# MainBoard.net
KiCad netlist of a schematic drawn in Altium Designer
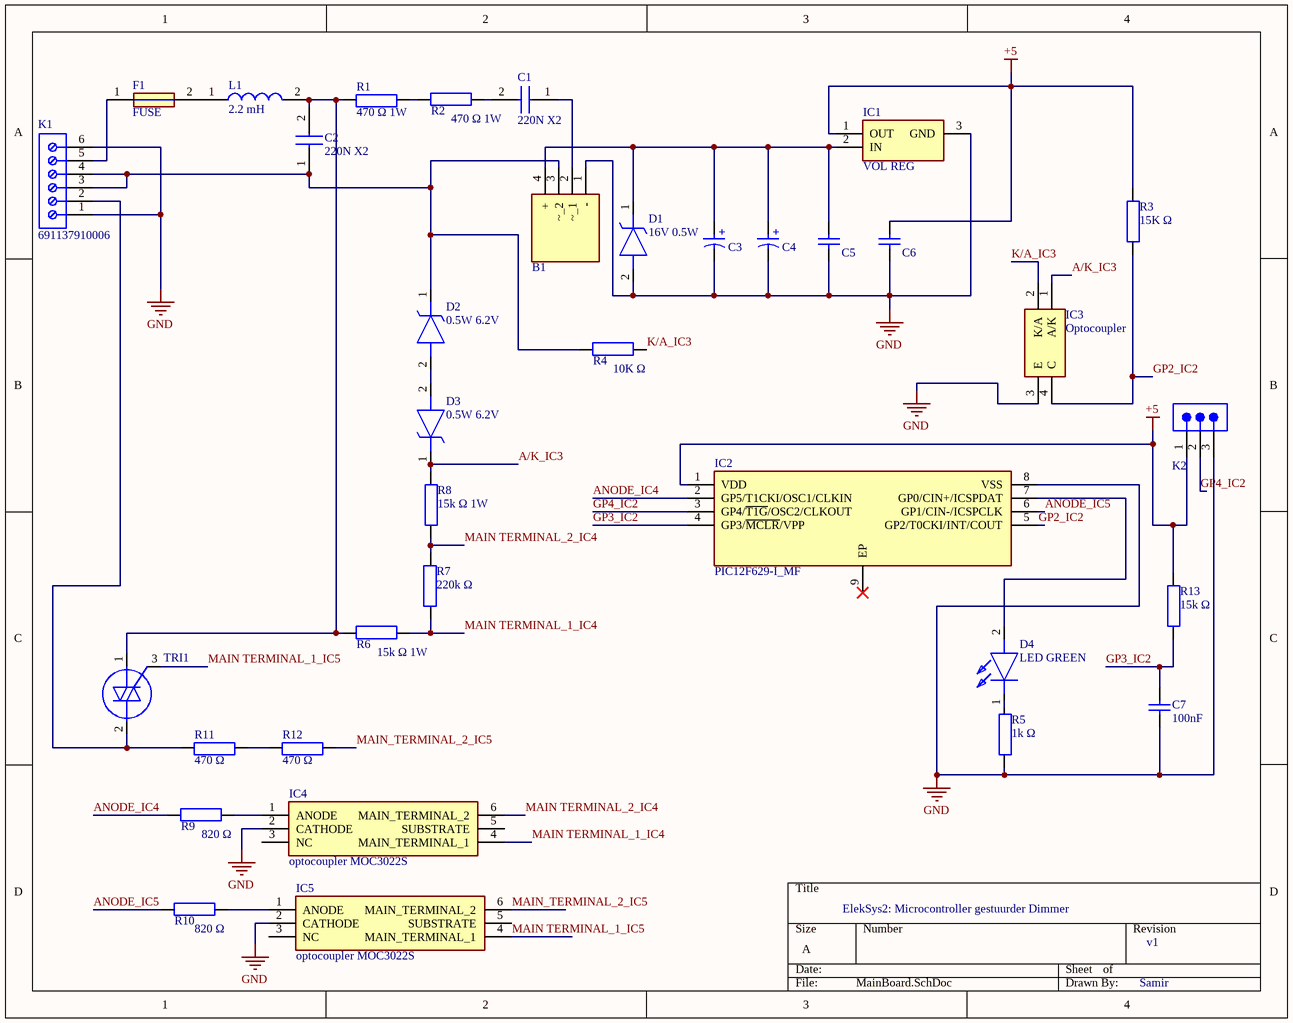
[diagram p0: MainBoard.SchDoc]

(export (version "E")
  (design (tool "Eeschema 10.0.6"))
  (components
    (comp (ref "B1")
      (value "~")
      (footprint "PCB_Lib:TO508P370X2000X1310-4P")
      (description "Bridge Rectifier GBUA10M-BP")
      (fields (field (name "MANUFACTURER_PART_NUMBER") "GBUA10M-BP"))
      (libsource (lib "MainBoardLib") (part "GBUA10M-BP"))
    )
    (comp (ref "C1")
      (value "220N X2")
      (footprint "PCB_Lib:B32932A_(18_x_8.5)")
      (description "Capacitor B32932A3224K189")
      (fields
        (field (name "MANUFACTURER_PART_NUMBER") "B32932A3224K189")
        (field (name "MOUSER PART NUMBER") "871-B32932A3224K189")
      )
      (libsource (lib "MainBoardLib") (part "220N X2 safetycap"))
    )
    (comp (ref "C2")
      (value "220N X2")
      (footprint "PCB_Lib:B32932A_(18_x_8.5)")
      (description "Capacitor B32932A3224K189")
      (fields
        (field (name "MANUFACTURER_PART_NUMBER") "B32932A3224K189")
        (field (name "MOUSER PART NUMBER") "871-B32932A3224K189")
      )
      (libsource (lib "MainBoardLib") (part "220N X2 safetycap"))
    )
    (comp (ref "C3")
      (value "220uF")
      (footprint "WCAP-ATG8_D8H11.5")
      (description "WCAP-ATG8 Aluminum Electrolytic Capacitor, Radial, THT, D8 x H11.5mm, 220uF, 35V")
      (fields
        (field (name "MANUFACTURER PART NUMBER") "860010574011")
        (field (name "MANUFACTURER") "Wurth Elektronik")
      )
      (libsource (lib "MainBoardLib") (part "Elco D8-H11.5"))
    )
    (comp (ref "C4")
      (value "220uF")
      (footprint "WCAP-ATG8_D8H11.5")
      (description "WCAP-ATG8 Aluminum Electrolytic Capacitor, Radial, THT, D8 x H11.5mm, 220uF, 35V")
      (fields
        (field (name "MANUFACTURER PART NUMBER") "860010574011")
        (field (name "MANUFACTURER") "Wurth Elektronik")
      )
      (libsource (lib "MainBoardLib") (part "Elco D8-H11.5"))
    )
    (comp (ref "C5")
      (value "100nF")
      (footprint "WCAP-CSGP_0805_L2W1.25H0.8_Reflow")
      (description "WCAP-CSGP Multilayer Ceramic Chip Capacitor, General Purpose, size 0805, X7R, 100nF, 50VDC")
      (fields
        (field (name "MANUFACTURER PART NUMBER") "885012207098")
        (field (name "MANUFACTURER") "Wurth Elektronik")
      )
      (libsource (lib "MainBoardLib") (part "CeramicCap 0805"))
    )
    (comp (ref "C6")
      (value "100nF")
      (footprint "WCAP-CSGP_0805_L2W1.25H0.8_Reflow")
      (description "WCAP-CSGP Multilayer Ceramic Chip Capacitor, General Purpose, size 0805, X7R, 100nF, 50VDC")
      (fields
        (field (name "MANUFACTURER PART NUMBER") "885012207098")
        (field (name "MANUFACTURER") "Wurth Elektronik")
      )
      (libsource (lib "MainBoardLib") (part "CeramicCap 0805"))
    )
    (comp (ref "C7")
      (value "100nF")
      (footprint "WCAP-CSGP_0805_L2W1.25H0.8_Reflow")
      (description "WCAP-CSGP Multilayer Ceramic Chip Capacitor, General Purpose, size 0805, X7R, 100nF, 50VDC")
      (fields
        (field (name "MANUFACTURER PART NUMBER") "885012207098")
        (field (name "MANUFACTURER") "Wurth Elektronik")
      )
      (libsource (lib "MainBoardLib") (part "CeramicCap 0805"))
    )
    (comp (ref "D1")
      (value "16V 0.5W")
      (footprint "PCB_Lib:DIOM5226X220N")
      (description "Zener Diode\r\nSZ1SMA5930BT3G")
      (fields
        (field (name "MANUFACTURER_PART_NUMBER") "SZ1SMA5930BT3G")
        (field (name "MOUSER PART NUMBER") "863-SZ1SMA5930BT3G")
      )
      (libsource (lib "MainBoardLib") (part "Zener 16V 0.5W"))
    )
    (comp (ref "D2")
      (value "0.5W 6.2V")
      (footprint "PCB_Lib:Zener Diodes ZEN REG 0.5W 6.2V")
      (description "Zener Diode\r\nSZMMSZ4691T1G")
      (fields
        (field (name "MANUFACTURER_PART_NUMBER") "SZMMSZ4691T1G")
        (field (name "MOUSER PART NUMBER") "863-SZMMSZ4691T1G")
      )
      (libsource (lib "MainBoardLib") (part "Zener Diodes ZEN REG 0.5W 6.2V"))
    )
    (comp (ref "D3")
      (value "0.5W 6.2V")
      (footprint "PCB_Lib:Zener Diodes ZEN REG 0.5W 6.2V")
      (description "Zener Diode\r\nSZMMSZ4691T1G")
      (fields
        (field (name "MANUFACTURER_PART_NUMBER") "SZMMSZ4691T1G")
        (field (name "MOUSER PART NUMBER") "863-SZMMSZ4691T1G")
      )
      (libsource (lib "MainBoardLib") (part "Zener Diodes ZEN REG 0.5W 6.2V"))
    )
    (comp (ref "D4")
      (value "LED GREEN")
      (footprint "PCB_Lib:LED 0805")
      (description "LED HSMG-C170")
      (fields
        (field (name "MANUFACTURER_PART_NUMBER") "HSMG-C170")
        (field (name "MOUSER PART NUMBER") "630-HSMG-C170")
      )
      (libsource (lib "MainBoardLib") (part "LED GREEN"))
    )
    (comp (ref "F1")
      (value "FUSE")
      (footprint "PCB_Lib:FUSE MRT")
      (description "Fuse MRT_1.6_AMMO")
      (fields
        (field (name "MANUFACTURER_PART_NUMBER") "MRT 1.6 AMMO")
        (field (name "MOUSER PART NUMBER") "530-MRT1.6AMMO")
      )
      (libsource (lib "MainBoardLib") (part "FUSE MRT_1.6_AMMO"))
    )
    (comp (ref "IC1")
      (value "VOL REG")
      (footprint "PCB_Lib:Vol reg")
      (description "Integrated Circuit LM3480IM3X-5.0_NOPB")
      (fields
        (field (name "MANUFACTURER_PART_NUMBER") "LM3480IM3X-5.0/NOPB")
        (field (name "MOUSER PART NUMBER") "926-LM3480IM3X50NOPB")
      )
      (libsource (lib "MainBoardLib") (part "VOL REG"))
    )
    (comp (ref "IC2")
      (value "PIC12F629-I_MF")
      (footprint "PCB_Lib:PIC12F629-I_MF")
      (description "Integrated Circuit")
      (fields
        (field (name "MANUFACTURER_PART_NUMBER") "PIC12F629-I/MF")
        (field (name "MOUSER PART NUMBER") "579-PIC12F629-I/MF")
      )
      (libsource (lib "MainBoardLib") (part "PIC12F629-I_MF"))
    )
    (comp (ref "IC3")
      (value "Optocoupler")
      (footprint "PCB_Lib:optocoupler smd")
      (description "Inductor SFH6206-3T")
      (fields
        (field (name "MANUFACTURER_PART_NUMBER") "SFH6206-3T")
        (field (name "MOUSER PART NUMBER") "782-SFH6206-3T")
      )
      (libsource (lib "MainBoardLib") (part "optocoupler smd"))
    )
    (comp (ref "IC4")
      (value "optocoupler MOC3022S")
      (footprint "PCB_Lib:optoucoupler MOC3022S")
      (description "integrated circuit")
      (fields
        (field (name "MANUFACTURER_PART_NUMBER") "MOC3022S")
        (field (name "MOUSER PART NUMBER") "859-MOC3022S")
      )
      (libsource (lib "MainBoardLib") (part "optocoupler MOC3022S"))
    )
    (comp (ref "IC5")
      (value "optocoupler MOC3022S")
      (footprint "PCB_Lib:optoucoupler MOC3022S")
      (description "integrated circuit")
      (fields
        (field (name "MANUFACTURER_PART_NUMBER") "MOC3022S")
        (field (name "MOUSER PART NUMBER") "859-MOC3022S")
      )
      (libsource (lib "MainBoardLib") (part "optocoupler MOC3022S"))
    )
    (comp (ref "K1")
      (value "691137910006")
      (footprint "691137910006")
      (libsource (lib "MainBoardLib") (part "connector"))
    )
    (comp (ref "K2")
      (value "61300311121")
      (footprint "connector 3p M")
      (description "WR-PHD Pin Header, THT, Vertical, pitch 2.54mm, 1 Row, 3P 61300311121")
      (fields (field (name "MANUFACTURER") "Wurth Elektronik"))
      (libsource (lib "MainBoardLib") (part "3P connector"))
    )
    (comp (ref "L1")
      (value "2.2 mH")
      (footprint "PCB_Lib:2.2mH inductor")
      (description "Inductor  1140-222k-sc\r\n140-222K-RC")
      (fields
        (field (name "MANUFACTURER_PART_NUMBER") "1140-222K-RC")
        (field (name "MOUSER PART NUMBER") "542-1140-222K-RC")
      )
      (libsource (lib "MainBoardLib") (part "2mH2 inductor"))
    )
    (comp (ref "R1")
      (value "470 Ω 1W")
      (footprint "PCB_Lib:RES_THT_1W")
      (fields
        (field (name "MANUFACTURER PART NUMBER") "560050320001")
        (field (name "MANUFACTURER") "Wurth Elektronik")
      )
      (libsource (lib "") (part "Resistor THT 1W_2"))
    )
    (comp (ref "R2")
      (value "470 Ω 1W")
      (footprint "PCB_Lib:RES_THT_1W")
      (fields
        (field (name "MANUFACTURER PART NUMBER") "560050320001")
        (field (name "MANUFACTURER") "Wurth Elektronik")
      )
      (libsource (lib "MainBoardLib") (part "Resistor THT 1W"))
    )
    (comp (ref "R3")
      (value "15K Ω")
      (footprint "PCB_Lib:Res 0805")
      (description "WRIS-KSKE Thick Film Resistor, SMT, size 0805, 0.33W, 0.1Ω, +/-1%")
      (fields
        (field (name "MANUFACTURER PART NUMBER") "560050320001")
        (field (name "MANUFACTURER") "Wurth Elektronik")
      )
      (libsource (lib "MainBoardLib") (part "Resistor 0805"))
    )
    (comp (ref "R4")
      (value "10K Ω")
      (footprint "Res 0805")
      (description "WRIS-KSKE Thick Film Resistor, SMT, size 0805, 0.33W, 0.1Ω, +/-1%")
      (fields
        (field (name "MANUFACTURER PART NUMBER") "560050320001")
        (field (name "MANUFACTURER") "Wurth Elektronik")
      )
      (libsource (lib "") (part "Resistor 0805_1"))
    )
    (comp (ref "R5")
      (value "1k Ω")
      (footprint "PCB_Lib:Res 0805")
      (description "WRIS-KSKE Thick Film Resistor, SMT, size 0805, 0.33W, 0.1Ω, +/-1%")
      (fields
        (field (name "MANUFACTURER PART NUMBER") "560050320001")
        (field (name "MANUFACTURER") "Wurth Elektronik")
      )
      (libsource (lib "MainBoardLib") (part "Resistor 0805"))
    )
    (comp (ref "R6")
      (value "15k Ω 1W")
      (footprint "PCB_Lib:RES_THT_1W")
      (fields
        (field (name "MANUFACTURER PART NUMBER") "560050320001")
        (field (name "MANUFACTURER") "Wurth Elektronik")
      )
      (libsource (lib "MainBoardLib") (part "Resistor THT 1W"))
    )
    (comp (ref "R7")
      (value "220k Ω")
      (footprint "PCB_Lib:Res 0805")
      (description "WRIS-KSKE Thick Film Resistor, SMT, size 0805, 0.33W, 0.1Ω, +/-1%")
      (fields
        (field (name "MANUFACTURER PART NUMBER") "560050320001")
        (field (name "MANUFACTURER") "Wurth Elektronik")
      )
      (libsource (lib "") (part "Resistor 0805_3"))
    )
    (comp (ref "R8")
      (value "15k Ω 1W")
      (footprint "PCB_Lib:RES_THT_1W")
      (fields
        (field (name "MANUFACTURER PART NUMBER") "560050320001")
        (field (name "MANUFACTURER") "Wurth Elektronik")
      )
      (libsource (lib "") (part "Resistor THT 1W_1"))
    )
    (comp (ref "R9")
      (value "820 Ω")
      (footprint "PCB_Lib:Res 0805")
      (description "WRIS-KSKE Thick Film Resistor, SMT, size 0805, 0.33W, 0.1Ω, +/-1%")
      (fields
        (field (name "MANUFACTURER PART NUMBER") "560050320001")
        (field (name "MANUFACTURER") "Wurth Elektronik")
      )
      (libsource (lib "") (part "Resistor 0805_1"))
    )
    (comp (ref "R10")
      (value "820 Ω")
      (footprint "PCB_Lib:Res 0805")
      (description "WRIS-KSKE Thick Film Resistor, SMT, size 0805, 0.33W, 0.1Ω, +/-1%")
      (fields
        (field (name "MANUFACTURER PART NUMBER") "560050320001")
        (field (name "MANUFACTURER") "Wurth Elektronik")
      )
      (libsource (lib "") (part "Resistor 0805_1"))
    )
    (comp (ref "R11")
      (value "470 Ω")
      (footprint "PCB_Lib:Res 0805")
      (description "WRIS-KSKE Thick Film Resistor, SMT, size 0805, 0.33W, 0.1Ω, +/-1%")
      (fields
        (field (name "MANUFACTURER PART NUMBER") "560050320001")
        (field (name "MANUFACTURER") "Wurth Elektronik")
      )
      (libsource (lib "") (part "Resistor 0805_2"))
    )
    (comp (ref "R12")
      (value "470 Ω")
      (footprint "PCB_Lib:Res 0805")
      (description "WRIS-KSKE Thick Film Resistor, SMT, size 0805, 0.33W, 0.1Ω, +/-1%")
      (fields
        (field (name "MANUFACTURER PART NUMBER") "560050320001")
        (field (name "MANUFACTURER") "Wurth Elektronik")
      )
      (libsource (lib "") (part "Resistor 0805_2"))
    )
    (comp (ref "R13")
      (value "15k Ω")
      (footprint "PCB_Lib:Res 0805")
      (description "WRIS-KSKE Thick Film Resistor, SMT, size 0805, 0.33W, 0.1Ω, +/-1%")
      (fields
        (field (name "MANUFACTURER PART NUMBER") "560050320001")
        (field (name "MANUFACTURER") "Wurth Elektronik")
      )
      (libsource (lib "MainBoardLib") (part "Resistor 0805"))
    )
    (comp (ref "TRI1")
      (value "BT137S-600,118")
      (footprint "triac bt137")
      (description "Triac BT137S-600,118")
      (fields (field (name "MOUSER PART NUMBER") "771-BT137S-600118"))
      (libsource (lib "MainBoardLib") (part "triac BT137S-600,118"))
    )
  )
  (nets
    (net (code "1") (name "+5") (class "Default")
      (node (ref "C6") (pin "2") (pinfunction "2_2") (pintype "passive"))
      (node (ref "IC1") (pin "1") (pinfunction "OUT_1") (pintype "passive"))
      (node (ref "IC2") (pin "1") (pinfunction "VDD_1") (pintype "passive"))
      (node (ref "K2") (pin "1") (pinfunction "1_1") (pintype "passive"))
      (node (ref "R13") (pin "1") (pinfunction "1_1") (pintype "passive"))
      (node (ref "R3") (pin "1") (pinfunction "1_1") (pintype "passive"))
    )
    (net (code "2") (name "/ANODE_IC4") (class "Default")
      (node (ref "IC2") (pin "2") (pinfunction "GP5/T1CKI/OSC1/CLKIN_2") (pintype "passive"))
      (node (ref "R9") (pin "1") (pinfunction "1_1") (pintype "passive"))
    )
    (net (code "3") (name "/ANODE_IC5") (class "Default")
      (node (ref "IC2") (pin "6") (pinfunction "GP1/CIN-/ICSPCLK_6") (pintype "passive"))
      (node (ref "R10") (pin "1") (pinfunction "1_1") (pintype "passive"))
    )
    (net (code "4") (name "/A{slash}K_IC3") (class "Default")
      (node (ref "D3") (pin "1") (pinfunction "K_1") (pintype "passive"))
      (node (ref "IC3") (pin "1") (pinfunction "A/K_1") (pintype "passive"))
      (node (ref "R8") (pin "1") (pinfunction "1_1") (pintype "passive"))
    )
    (net (code "5") (name "/GP2_IC2") (class "Default")
      (node (ref "IC2") (pin "5") (pinfunction "GP2/T0CKI/INT/COUT_5") (pintype "passive"))
      (node (ref "IC3") (pin "4") (pinfunction "C_4") (pintype "passive"))
      (node (ref "R3") (pin "2") (pinfunction "2_2") (pintype "passive"))
    )
    (net (code "6") (name "/GP3_IC2") (class "Default")
      (node (ref "C7") (pin "1") (pinfunction "1_1") (pintype "passive"))
      (node (ref "IC2") (pin "4") (pinfunction "GP3/~{MCLR}/VPP_4") (pintype "passive"))
      (node (ref "R13") (pin "2") (pinfunction "2_2") (pintype "passive"))
    )
    (net (code "7") (name "/GP4_IC2") (class "Default")
      (node (ref "IC2") (pin "3") (pinfunction "GP4/~{T1G}/OSC2/CLKOUT_3") (pintype "passive"))
      (node (ref "K2") (pin "2") (pinfunction "2_2") (pintype "passive"))
    )
    (net (code "8") (name "/K{slash}A_IC3") (class "Default")
      (node (ref "IC3") (pin "2") (pinfunction "K/A_2") (pintype "passive"))
      (node (ref "R4") (pin "2") (pinfunction "2_2") (pintype "passive"))
    )
    (net (code "9") (name "/MAIN TERMINAL_1_IC4") (class "Default")
      (node (ref "IC4") (pin "4") (pinfunction "MAIN_TERMINAL_1_4") (pintype "passive"))
      (node (ref "R6") (pin "2") (pinfunction "2_2") (pintype "passive"))
      (node (ref "R7") (pin "1") (pinfunction "1_1") (pintype "passive"))
    )
    (net (code "10") (name "/MAIN TERMINAL_1_IC5") (class "Default")
      (node (ref "IC5") (pin "4") (pinfunction "MAIN_TERMINAL_1_4") (pintype "passive"))
      (node (ref "TRI1") (pin "3") (pinfunction "G_3") (pintype "passive"))
    )
    (net (code "11") (name "/MAIN TERMINAL_2_IC4") (class "Default")
      (node (ref "IC4") (pin "6") (pinfunction "MAIN_TERMINAL_2_6") (pintype "passive"))
      (node (ref "R7") (pin "2") (pinfunction "2_2") (pintype "passive"))
      (node (ref "R8") (pin "2") (pinfunction "2_2") (pintype "passive"))
    )
    (net (code "12") (name "/MAIN_TERMINAL_2_IC5") (class "Default")
      (node (ref "IC5") (pin "6") (pinfunction "MAIN_TERMINAL_2_6") (pintype "passive"))
      (node (ref "R12") (pin "1") (pinfunction "1_1") (pintype "passive"))
    )
    (net (code "13") (name "GND") (class "Default")
      (node (ref "B1") (pin "1") (pinfunction "-_1") (pintype "passive"))
      (node (ref "C3") (pin "2") (pinfunction "N_2") (pintype "passive"))
      (node (ref "C4") (pin "2") (pinfunction "N_2") (pintype "passive"))
      (node (ref "C5") (pin "1") (pinfunction "1_1") (pintype "passive"))
      (node (ref "C6") (pin "1") (pinfunction "1_1") (pintype "passive"))
      (node (ref "C7") (pin "2") (pinfunction "2_2") (pintype "passive"))
      (node (ref "D1") (pin "2") (pinfunction "A_2") (pintype "passive"))
      (node (ref "IC1") (pin "3") (pinfunction "GND_3") (pintype "passive"))
      (node (ref "IC2") (pin "8") (pinfunction "VSS_8") (pintype "passive"))
      (node (ref "IC3") (pin "3") (pinfunction "E_3") (pintype "passive"))
      (node (ref "IC4") (pin "2") (pinfunction "CATHODE_2") (pintype "passive"))
      (node (ref "IC5") (pin "2") (pinfunction "CATHODE_2") (pintype "passive"))
      (node (ref "K1") (pin "1") (pinfunction "1_1") (pintype "passive"))
      (node (ref "K1") (pin "6") (pinfunction "6_6") (pintype "passive"))
      (node (ref "K2") (pin "3") (pinfunction "3_3") (pintype "passive"))
      (node (ref "R5") (pin "2") (pinfunction "2_2") (pintype "passive"))
    )
    (net (code "14") (name "Net-(B1-+)") (class "Default")
      (node (ref "B1") (pin "4") (pinfunction "+_4") (pintype "passive"))
      (node (ref "C3") (pin "1") (pinfunction "P_1") (pintype "passive"))
      (node (ref "C4") (pin "1") (pinfunction "P_1") (pintype "passive"))
      (node (ref "C5") (pin "2") (pinfunction "2_2") (pintype "passive"))
      (node (ref "D1") (pin "1") (pinfunction "K_1") (pintype "passive"))
      (node (ref "IC1") (pin "2") (pinfunction "IN_2") (pintype "passive"))
    )
    (net (code "15") (name "Net-(B1-~_1)") (class "Default")
      (node (ref "B1") (pin "2") (pinfunction "~_1_2") (pintype "passive"))
      (node (ref "C1") (pin "1") (pinfunction "1_1") (pintype "passive"))
    )
    (net (code "16") (name "Net-(B1-~_2)") (class "Default")
      (node (ref "B1") (pin "3") (pinfunction "~_2_3") (pintype "passive"))
      (node (ref "C2") (pin "1") (pinfunction "1_1") (pintype "passive"))
      (node (ref "D2") (pin "1") (pinfunction "K_1") (pintype "passive"))
      (node (ref "K1") (pin "3") (pinfunction "3_3") (pintype "passive"))
      (node (ref "K1") (pin "4") (pinfunction "4_4") (pintype "passive"))
      (node (ref "R4") (pin "1") (pinfunction "1_1") (pintype "passive"))
    )
    (net (code "17") (name "Net-(C1-Pad2)") (class "Default")
      (node (ref "C1") (pin "2") (pinfunction "2_2") (pintype "passive"))
      (node (ref "R2") (pin "2") (pinfunction "2_2") (pintype "passive"))
    )
    (net (code "18") (name "Net-(D2-A)") (class "Default")
      (node (ref "D2") (pin "2") (pinfunction "A_2") (pintype "passive"))
      (node (ref "D3") (pin "2") (pinfunction "A_2") (pintype "passive"))
    )
    (net (code "19") (name "Net-(D4-A)") (class "Default")
      (node (ref "D4") (pin "2") (pinfunction "A_2") (pintype "passive"))
      (node (ref "IC2") (pin "7") (pinfunction "GP0/CIN+/ICSPDAT_7") (pintype "passive"))
    )
    (net (code "20") (name "Net-(D4-K)") (class "Default")
      (node (ref "D4") (pin "1") (pinfunction "K_1") (pintype "passive"))
      (node (ref "R5") (pin "1") (pinfunction "1_1") (pintype "passive"))
    )
    (net (code "21") (name "Net-(F1-Pad1)") (class "Default")
      (node (ref "F1") (pin "1") (pinfunction "1_1") (pintype "passive"))
      (node (ref "K1") (pin "5") (pinfunction "5_5") (pintype "passive"))
    )
    (net (code "22") (name "Net-(F1-Pad2)") (class "Default")
      (node (ref "F1") (pin "2") (pinfunction "2_2") (pintype "passive"))
      (node (ref "L1") (pin "1") (pinfunction "1_1") (pintype "passive"))
    )
    (net (code "23") (name "Net-(IC4-ANODE)") (class "Default")
      (node (ref "IC4") (pin "1") (pinfunction "ANODE_1") (pintype "passive"))
      (node (ref "R9") (pin "2") (pinfunction "2_2") (pintype "passive"))
    )
    (net (code "24") (name "Net-(IC5-ANODE)") (class "Default")
      (node (ref "IC5") (pin "1") (pinfunction "ANODE_1") (pintype "passive"))
      (node (ref "R10") (pin "2") (pinfunction "2_2") (pintype "passive"))
    )
    (net (code "25") (name "Net-(R1-Pad1)") (class "Default")
      (node (ref "R1") (pin "1") (pinfunction "1_1") (pintype "passive"))
      (node (ref "R2") (pin "1") (pinfunction "1_1") (pintype "passive"))
    )
    (net (code "26") (name "Net-(R11-Pad1)") (class "Default")
      (node (ref "R11") (pin "1") (pinfunction "1_1") (pintype "passive"))
      (node (ref "R12") (pin "2") (pinfunction "2_2") (pintype "passive"))
    )
    (net (code "27") (name "Net-(TRI1-MT1)") (class "Default")
      (node (ref "C2") (pin "2") (pinfunction "2_2") (pintype "passive"))
      (node (ref "L1") (pin "2") (pinfunction "2_2") (pintype "passive"))
      (node (ref "R1") (pin "2") (pinfunction "2_2") (pintype "passive"))
      (node (ref "R6") (pin "1") (pinfunction "1_1") (pintype "passive"))
      (node (ref "TRI1") (pin "1") (pinfunction "MT1_1") (pintype "passive"))
    )
    (net (code "28") (name "Net-(TRI1-MT2)") (class "Default")
      (node (ref "K1") (pin "2") (pinfunction "2_2") (pintype "passive"))
      (node (ref "R11") (pin "2") (pinfunction "2_2") (pintype "passive"))
      (node (ref "TRI1") (pin "2") (pinfunction "MT2_2") (pintype "passive"))
    )
    (net (code "29") (name "unconnected-(IC2-EP-Pad9)") (class "Default")
      (node (ref "IC2") (pin "9") (pinfunction "EP_9") (pintype "passive+no_connect"))
    )
    (net (code "30") (name "unconnected-(IC4-NC-Pad3)") (class "Default")
      (node (ref "IC4") (pin "3") (pinfunction "NC_3") (pintype "passive"))
    )
    (net (code "31") (name "unconnected-(IC4-SUBSTRATE-Pad5)") (class "Default")
      (node (ref "IC4") (pin "5") (pinfunction "SUBSTRATE_5") (pintype "passive"))
    )
    (net (code "32") (name "unconnected-(IC5-NC-Pad3)") (class "Default")
      (node (ref "IC5") (pin "3") (pinfunction "NC_3") (pintype "passive"))
    )
    (net (code "33") (name "unconnected-(IC5-SUBSTRATE-Pad5)") (class "Default")
      (node (ref "IC5") (pin "5") (pinfunction "SUBSTRATE_5") (pintype "passive"))
    )
  )
)
